# Sch_Add.net
KiCad netlist of a schematic drawn in Altium Designer
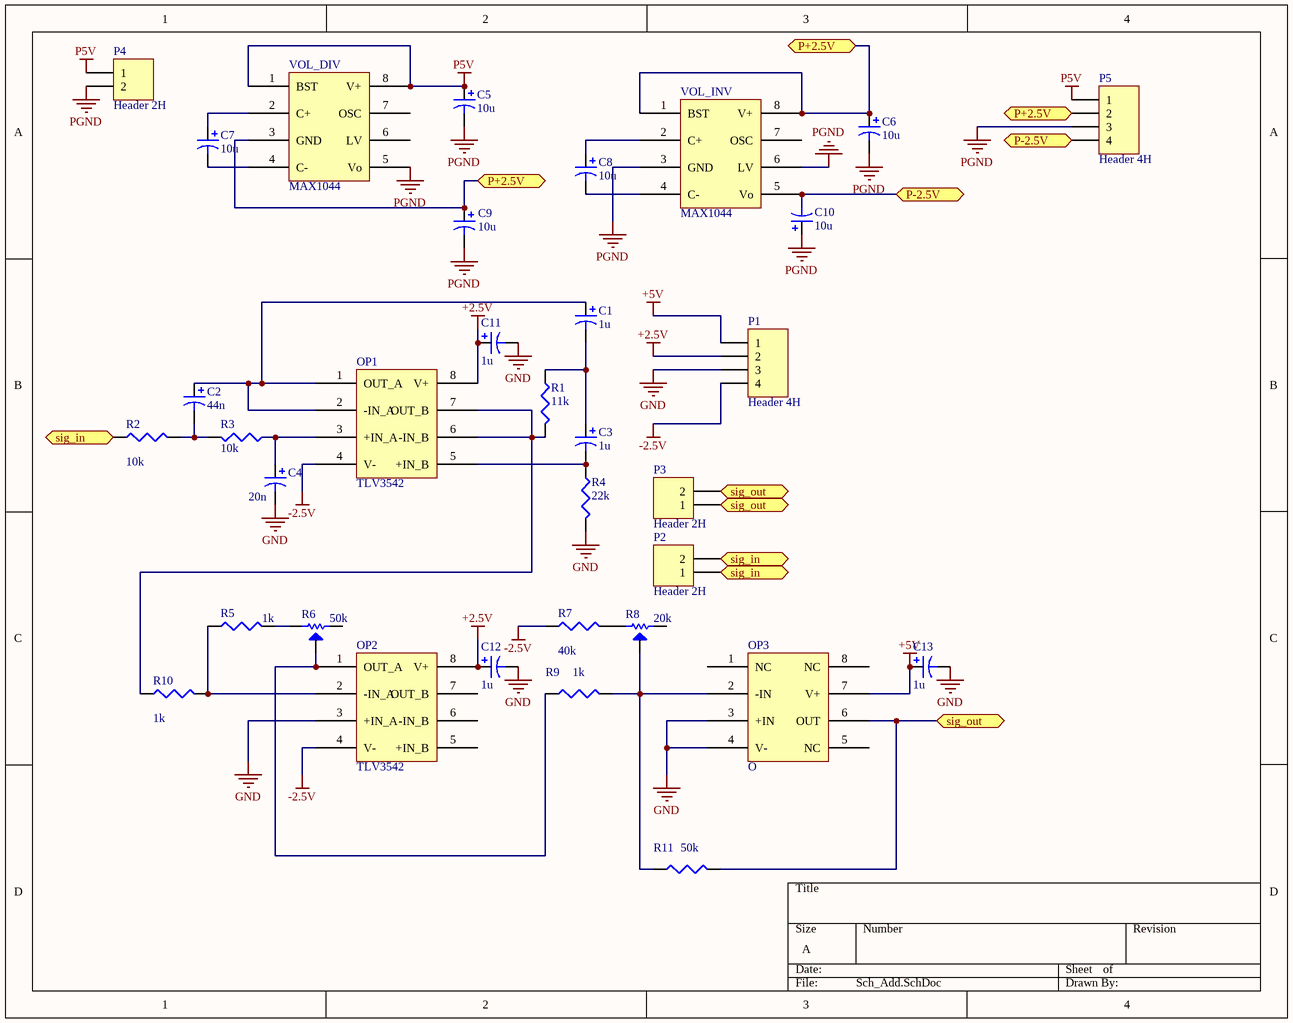
[diagram p0: Sch_Add.SchDoc]

(export (version "E")
  (design (tool "Eeschema 10.0.6"))
  (components
    (comp (ref "C1")
      (value "1u")
      (footprint "C0805")
      (description "Polarized Capacitor (Surface Mount)")
      (fields (field (name "Comment") "Cap Pol3") (field (name "PUBLISHER") "Altium Limited"))
      (libsource (lib "Miscellaneous Devices") (part "Cap Pol3"))
    )
    (comp (ref "C2")
      (value "44n")
      (footprint "C0805")
      (description "Polarized Capacitor (Surface Mount)")
      (fields (field (name "Comment") "Cap Pol3") (field (name "PUBLISHER") "Altium Limited"))
      (libsource (lib "Miscellaneous Devices") (part "Cap Pol3"))
    )
    (comp (ref "C3")
      (value "1u")
      (footprint "C0805")
      (description "Polarized Capacitor (Surface Mount)")
      (fields (field (name "Comment") "Cap Pol3") (field (name "PUBLISHER") "Altium Limited"))
      (libsource (lib "Miscellaneous Devices") (part "Cap Pol3"))
    )
    (comp (ref "C4")
      (value "20n")
      (footprint "C0805")
      (description "Polarized Capacitor (Surface Mount)")
      (fields (field (name "Comment") "Cap Pol3") (field (name "PUBLISHER") "Altium Limited"))
      (libsource (lib "Miscellaneous Devices") (part "Cap Pol3"))
    )
    (comp (ref "C5")
      (value "10u")
      (footprint "C0805")
      (description "Polarized Capacitor (Surface Mount)")
      (fields (field (name "Comment") "Cap Pol3") (field (name "PUBLISHER") "Altium Limited"))
      (libsource (lib "Miscellaneous Devices") (part "Cap Pol3"))
    )
    (comp (ref "C6")
      (value "10u")
      (footprint "C0805")
      (description "Polarized Capacitor (Surface Mount)")
      (fields (field (name "Comment") "Cap Pol3") (field (name "PUBLISHER") "Altium Limited"))
      (libsource (lib "Miscellaneous Devices") (part "Cap Pol3"))
    )
    (comp (ref "C7")
      (value "10u")
      (footprint "C0805")
      (description "Polarized Capacitor (Surface Mount)")
      (fields (field (name "Comment") "Cap Pol3") (field (name "PUBLISHER") "Altium Limited"))
      (libsource (lib "Miscellaneous Devices") (part "Cap Pol3"))
    )
    (comp (ref "C8")
      (value "10u")
      (footprint "C0805")
      (description "Polarized Capacitor (Surface Mount)")
      (fields (field (name "Comment") "Cap Pol3") (field (name "PUBLISHER") "Altium Limited"))
      (libsource (lib "Miscellaneous Devices") (part "Cap Pol3"))
    )
    (comp (ref "C9")
      (value "10u")
      (footprint "C0805")
      (description "Polarized Capacitor (Surface Mount)")
      (fields (field (name "Comment") "Cap Pol3") (field (name "PUBLISHER") "Altium Limited"))
      (libsource (lib "Miscellaneous Devices") (part "Cap Pol3"))
    )
    (comp (ref "C10")
      (value "10u")
      (footprint "C0805")
      (description "Polarized Capacitor (Surface Mount)")
      (fields (field (name "Comment") "Cap Pol3") (field (name "PUBLISHER") "Altium Limited"))
      (libsource (lib "Miscellaneous Devices") (part "Cap Pol3"))
    )
    (comp (ref "C11")
      (value "1u")
      (footprint "C0805")
      (description "Polarized Capacitor (Surface Mount)")
      (fields (field (name "Comment") "Cap Pol3") (field (name "PUBLISHER") "Altium Limited"))
      (libsource (lib "Miscellaneous Devices") (part "Cap Pol3"))
    )
    (comp (ref "C12")
      (value "1u")
      (footprint "C0805")
      (description "Polarized Capacitor (Surface Mount)")
      (fields (field (name "Comment") "Cap Pol3") (field (name "PUBLISHER") "Altium Limited"))
      (libsource (lib "Miscellaneous Devices") (part "Cap Pol3"))
    )
    (comp (ref "C13")
      (value "1u")
      (footprint "C0805")
      (description "Polarized Capacitor (Surface Mount)")
      (fields (field (name "Comment") "Cap Pol3") (field (name "PUBLISHER") "Altium Limited"))
      (libsource (lib "Miscellaneous Devices") (part "Cap Pol3"))
    )
    (comp (ref "OP1")
      (value "TLV3542")
      (footprint "SOIC127P600X175-8N")
      (libsource (lib "tlv3542") (part "TLV3542"))
    )
    (comp (ref "OP2")
      (value "TLV3542")
      (footprint "SOIC127P600X175-8N")
      (libsource (lib "tlv3542") (part "TLV3542"))
    )
    (comp (ref "OP3")
      (value "O")
      (footprint "SOIC127P600X175-8N")
      (libsource (lib "tlv3542") (part "OPA388IDR"))
    )
    (comp (ref "P1")
      (value "Header 4H")
      (footprint "HDR1X4H")
      (description "Header, 4-Pin, Right Angle")
      (fields (field (name "PUBLISHER") "Altium Limited"))
      (libsource (lib "Miscellaneous Connectors") (part "Header 4H"))
    )
    (comp (ref "P2")
      (value "Header 2H")
      (footprint "HDR1X2H")
      (description "Header, 2-Pin, Right Angle")
      (fields (field (name "PUBLISHER") "Altium Limited"))
      (libsource (lib "Miscellaneous Connectors") (part "Header 2H"))
    )
    (comp (ref "P3")
      (value "Header 2H")
      (footprint "HDR1X2H")
      (description "Header, 2-Pin, Right Angle")
      (fields (field (name "PUBLISHER") "Altium Limited"))
      (libsource (lib "Miscellaneous Connectors") (part "Header 2H"))
    )
    (comp (ref "P4")
      (value "Header 2H")
      (footprint "HDR1X2H")
      (description "Header, 2-Pin, Right Angle")
      (fields (field (name "PUBLISHER") "Altium Limited"))
      (libsource (lib "") (part "Header 2H_1"))
    )
    (comp (ref "P5")
      (value "Header 4H")
      (footprint "HDR1X4H")
      (description "Header, 4-Pin, Right Angle")
      (fields (field (name "PUBLISHER") "Altium Limited"))
      (libsource (lib "Miscellaneous Connectors") (part "Header 4H"))
    )
    (comp (ref "R1")
      (value "11k")
      (footprint "J1-0603")
      (description "Resistor")
      (fields (field (name "Comment") "Res3") (field (name "PUBLISHER") "Altium Limited"))
      (libsource (lib "Miscellaneous Devices") (part "Res3"))
    )
    (comp (ref "R2")
      (value "10k")
      (footprint "J1-0603")
      (description "Resistor")
      (fields (field (name "Comment") "Res3") (field (name "PUBLISHER") "Altium Limited"))
      (libsource (lib "Miscellaneous Devices") (part "Res3"))
    )
    (comp (ref "R3")
      (value "10k")
      (footprint "J1-0603")
      (description "Resistor")
      (fields (field (name "Comment") "Res3") (field (name "PUBLISHER") "Altium Limited"))
      (libsource (lib "Miscellaneous Devices") (part "Res3"))
    )
    (comp (ref "R4")
      (value "22k")
      (footprint "J1-0603")
      (description "Resistor")
      (fields (field (name "Comment") "Res3") (field (name "PUBLISHER") "Altium Limited"))
      (libsource (lib "Miscellaneous Devices") (part "Res3"))
    )
    (comp (ref "R5")
      (value "1k")
      (footprint "J1-0603")
      (description "Resistor")
      (fields (field (name "Comment") "Res3") (field (name "PUBLISHER") "Altium Limited"))
      (libsource (lib "Miscellaneous Devices") (part "Res3"))
    )
    (comp (ref "R6")
      (value "50k")
      (footprint "3362P")
      (fields (field (name "Comment") "5"))
      (libsource (lib "tlv3542") (part "Res_3362P"))
    )
    (comp (ref "R7")
      (value "40k")
      (footprint "J1-0603")
      (description "Resistor")
      (fields (field (name "Comment") "Res3") (field (name "PUBLISHER") "Altium Limited"))
      (libsource (lib "Miscellaneous Devices") (part "Res3"))
    )
    (comp (ref "R8")
      (value "20k")
      (footprint "3362P")
      (fields (field (name "Comment") "2"))
      (libsource (lib "tlv3542") (part "Res_3362P"))
    )
    (comp (ref "R9")
      (value "1k")
      (footprint "J1-0603")
      (description "Resistor")
      (fields (field (name "Comment") "Res3") (field (name "PUBLISHER") "Altium Limited"))
      (libsource (lib "Miscellaneous Devices") (part "Res3"))
    )
    (comp (ref "R10")
      (value "1k")
      (footprint "J1-0603")
      (description "Resistor")
      (fields (field (name "Comment") "Res3") (field (name "PUBLISHER") "Altium Limited"))
      (libsource (lib "Miscellaneous Devices") (part "Res3"))
    )
    (comp (ref "R11")
      (value "50k")
      (footprint "J1-0603")
      (description "Resistor")
      (fields (field (name "Comment") "Res3") (field (name "PUBLISHER") "Altium Limited"))
      (libsource (lib "Miscellaneous Devices") (part "Res3"))
    )
    (comp (ref "VOL_DIV")
      (value "MAX1044")
      (footprint "SOIC127P600X175-8N")
      (libsource (lib "tlv3542") (part "MAX1044"))
    )
    (comp (ref "VOL_INV")
      (value "MAX1044")
      (footprint "SOIC127P600X175-8N")
      (libsource (lib "tlv3542") (part "MAX1044"))
    )
  )
  (nets
    (net (code "1") (name "+2.5V") (class "Default")
      (node (ref "C11") (pin "1") (pinfunction "1_1") (pintype "passive"))
      (node (ref "C12") (pin "1") (pinfunction "1_1") (pintype "passive"))
      (node (ref "OP1") (pin "8") (pinfunction "V+_8") (pintype "passive"))
      (node (ref "OP2") (pin "8") (pinfunction "V+_8") (pintype "passive"))
      (node (ref "P1") (pin "2") (pinfunction "2_2") (pintype "passive"))
    )
    (net (code "2") (name "+5V") (class "Default")
      (node (ref "C13") (pin "1") (pinfunction "1_1") (pintype "passive"))
      (node (ref "OP3") (pin "7") (pinfunction "V+_7") (pintype "passive"))
      (node (ref "P1") (pin "1") (pinfunction "1_1") (pintype "passive"))
    )
    (net (code "3") (name "-2.5V") (class "Default")
      (node (ref "OP1") (pin "4") (pinfunction "V-_4") (pintype "passive"))
      (node (ref "OP2") (pin "4") (pinfunction "V-_4") (pintype "passive"))
      (node (ref "P1") (pin "4") (pinfunction "4_4") (pintype "passive"))
      (node (ref "R7") (pin "1") (pinfunction "1_1") (pintype "passive"))
    )
    (net (code "4") (name "/P+2.5V") (class "Default")
      (node (ref "C6") (pin "1") (pinfunction "1_1") (pintype "passive"))
      (node (ref "C9") (pin "1") (pinfunction "1_1") (pintype "passive"))
      (node (ref "P5") (pin "2") (pinfunction "2_2") (pintype "passive"))
      (node (ref "VOL_DIV") (pin "3") (pinfunction "GND_3") (pintype "passive"))
      (node (ref "VOL_INV") (pin "1") (pinfunction "BST_1") (pintype "passive"))
      (node (ref "VOL_INV") (pin "8") (pinfunction "V+_8") (pintype "passive"))
    )
    (net (code "5") (name "/P-2.5V") (class "Default")
      (node (ref "C10") (pin "2") (pinfunction "2_2") (pintype "passive"))
      (node (ref "P5") (pin "4") (pinfunction "4_4") (pintype "passive"))
      (node (ref "VOL_INV") (pin "5") (pinfunction "Vo_5") (pintype "passive"))
    )
    (net (code "6") (name "/sig_in") (class "Default")
      (node (ref "P2") (pin "1") (pinfunction "1_1") (pintype "passive"))
      (node (ref "P2") (pin "2") (pinfunction "2_2") (pintype "passive"))
      (node (ref "R2") (pin "1") (pinfunction "1_1") (pintype "passive"))
    )
    (net (code "7") (name "/sig_out") (class "Default")
      (node (ref "OP3") (pin "6") (pinfunction "OUT_6") (pintype "passive"))
      (node (ref "P3") (pin "1") (pinfunction "1_1") (pintype "passive"))
      (node (ref "P3") (pin "2") (pinfunction "2_2") (pintype "passive"))
      (node (ref "R11") (pin "2") (pinfunction "2_2") (pintype "passive"))
    )
    (net (code "8") (name "GND") (class "Default")
      (node (ref "C11") (pin "2") (pinfunction "2_2") (pintype "passive"))
      (node (ref "C12") (pin "2") (pinfunction "2_2") (pintype "passive"))
      (node (ref "C13") (pin "2") (pinfunction "2_2") (pintype "passive"))
      (node (ref "C4") (pin "2") (pinfunction "2_2") (pintype "passive"))
      (node (ref "OP2") (pin "3") (pinfunction "+IN_A_3") (pintype "passive"))
      (node (ref "OP3") (pin "3") (pinfunction "+IN_3") (pintype "passive"))
      (node (ref "OP3") (pin "4") (pinfunction "V-_4") (pintype "passive"))
      (node (ref "P1") (pin "3") (pinfunction "3_3") (pintype "passive"))
      (node (ref "R4") (pin "2") (pinfunction "2_2") (pintype "passive"))
    )
    (net (code "9") (name "Net-(C1-Pad2)") (class "Default")
      (node (ref "C1") (pin "2") (pinfunction "2_2") (pintype "passive"))
      (node (ref "C3") (pin "1") (pinfunction "1_1") (pintype "passive"))
      (node (ref "R1") (pin "1") (pinfunction "1_1") (pintype "passive"))
    )
    (net (code "10") (name "Net-(C2-Pad2)") (class "Default")
      (node (ref "C2") (pin "2") (pinfunction "2_2") (pintype "passive"))
      (node (ref "R2") (pin "2") (pinfunction "2_2") (pintype "passive"))
      (node (ref "R3") (pin "2") (pinfunction "2_2") (pintype "passive"))
    )
    (net (code "11") (name "Net-(OP1-+IN_A)") (class "Default")
      (node (ref "C4") (pin "1") (pinfunction "1_1") (pintype "passive"))
      (node (ref "OP1") (pin "3") (pinfunction "+IN_A_3") (pintype "passive"))
      (node (ref "R3") (pin "1") (pinfunction "1_1") (pintype "passive"))
    )
    (net (code "12") (name "Net-(OP1-+IN_B)") (class "Default")
      (node (ref "C3") (pin "2") (pinfunction "2_2") (pintype "passive"))
      (node (ref "OP1") (pin "5") (pinfunction "+IN_B_5") (pintype "passive"))
      (node (ref "R4") (pin "1") (pinfunction "1_1") (pintype "passive"))
    )
    (net (code "13") (name "Net-(OP1--IN_A)") (class "Default")
      (node (ref "C1") (pin "1") (pinfunction "1_1") (pintype "passive"))
      (node (ref "C2") (pin "1") (pinfunction "1_1") (pintype "passive"))
      (node (ref "OP1") (pin "1") (pinfunction "OUT_A_1") (pintype "passive"))
      (node (ref "OP1") (pin "2") (pinfunction "-IN_A_2") (pintype "passive"))
    )
    (net (code "14") (name "Net-(OP1--IN_B)") (class "Default")
      (node (ref "OP1") (pin "6") (pinfunction "-IN_B_6") (pintype "passive"))
      (node (ref "OP1") (pin "7") (pinfunction "OUT_B_7") (pintype "passive"))
      (node (ref "R1") (pin "2") (pinfunction "2_2") (pintype "passive"))
      (node (ref "R10") (pin "1") (pinfunction "1_1") (pintype "passive"))
    )
    (net (code "15") (name "Net-(OP2--IN_A)") (class "Default")
      (node (ref "OP2") (pin "2") (pinfunction "-IN_A_2") (pintype "passive"))
      (node (ref "R10") (pin "2") (pinfunction "2_2") (pintype "passive"))
      (node (ref "R5") (pin "1") (pinfunction "1_1") (pintype "passive"))
    )
    (net (code "16") (name "Net-(OP2-OUT_A)") (class "Default")
      (node (ref "OP2") (pin "1") (pinfunction "OUT_A_1") (pintype "passive"))
      (node (ref "R6") (pin "3") (pinfunction "3_3") (pintype "passive"))
      (node (ref "R9") (pin "1") (pinfunction "1_1") (pintype "passive"))
    )
    (net (code "17") (name "Net-(OP3--IN)") (class "Default")
      (node (ref "OP3") (pin "2") (pinfunction "-IN_2") (pintype "passive"))
      (node (ref "R11") (pin "1") (pinfunction "1_1") (pintype "passive"))
      (node (ref "R8") (pin "3") (pinfunction "3_3") (pintype "passive"))
      (node (ref "R9") (pin "2") (pinfunction "2_2") (pintype "passive"))
    )
    (net (code "18") (name "Net-(R5-Pad2)") (class "Default")
      (node (ref "R5") (pin "2") (pinfunction "2_2") (pintype "passive"))
      (node (ref "R6") (pin "1") (pinfunction "1_1") (pintype "passive"))
    )
    (net (code "19") (name "Net-(R7-Pad2)") (class "Default")
      (node (ref "R7") (pin "2") (pinfunction "2_2") (pintype "passive"))
      (node (ref "R8") (pin "1") (pinfunction "1_1") (pintype "passive"))
    )
    (net (code "20") (name "Net-(VOL_DIV-C+)") (class "Default")
      (node (ref "C7") (pin "1") (pinfunction "1_1") (pintype "passive"))
      (node (ref "VOL_DIV") (pin "2") (pinfunction "C+_2") (pintype "passive"))
    )
    (net (code "21") (name "Net-(VOL_DIV-C-)") (class "Default")
      (node (ref "C7") (pin "2") (pinfunction "2_2") (pintype "passive"))
      (node (ref "VOL_DIV") (pin "4") (pinfunction "C-_4") (pintype "passive"))
    )
    (net (code "22") (name "Net-(VOL_INV-C+)") (class "Default")
      (node (ref "C8") (pin "1") (pinfunction "1_1") (pintype "passive"))
      (node (ref "VOL_INV") (pin "2") (pinfunction "C+_2") (pintype "passive"))
    )
    (net (code "23") (name "Net-(VOL_INV-C-)") (class "Default")
      (node (ref "C8") (pin "2") (pinfunction "2_2") (pintype "passive"))
      (node (ref "VOL_INV") (pin "4") (pinfunction "C-_4") (pintype "passive"))
    )
    (net (code "24") (name "P5V") (class "Default")
      (node (ref "C5") (pin "1") (pinfunction "1_1") (pintype "passive"))
      (node (ref "P4") (pin "1") (pinfunction "1_1") (pintype "passive"))
      (node (ref "P5") (pin "1") (pinfunction "1_1") (pintype "passive"))
      (node (ref "VOL_DIV") (pin "1") (pinfunction "BST_1") (pintype "passive"))
      (node (ref "VOL_DIV") (pin "8") (pinfunction "V+_8") (pintype "passive"))
    )
    (net (code "25") (name "PGND") (class "Default")
      (node (ref "C10") (pin "1") (pinfunction "1_1") (pintype "passive"))
      (node (ref "C5") (pin "2") (pinfunction "2_2") (pintype "passive"))
      (node (ref "C6") (pin "2") (pinfunction "2_2") (pintype "passive"))
      (node (ref "C9") (pin "2") (pinfunction "2_2") (pintype "passive"))
      (node (ref "P4") (pin "2") (pinfunction "2_2") (pintype "passive"))
      (node (ref "P5") (pin "3") (pinfunction "3_3") (pintype "passive"))
      (node (ref "VOL_DIV") (pin "5") (pinfunction "Vo_5") (pintype "passive"))
      (node (ref "VOL_INV") (pin "3") (pinfunction "GND_3") (pintype "passive"))
      (node (ref "VOL_INV") (pin "6") (pinfunction "LV_6") (pintype "passive"))
    )
    (net (code "26") (name "unconnected-(OP2-+IN_B-Pad5)") (class "Default")
      (node (ref "OP2") (pin "5") (pinfunction "+IN_B_5") (pintype "passive"))
    )
    (net (code "27") (name "unconnected-(OP2--IN_B-Pad6)") (class "Default")
      (node (ref "OP2") (pin "6") (pinfunction "-IN_B_6") (pintype "passive"))
    )
    (net (code "28") (name "unconnected-(OP2-OUT_B-Pad7)") (class "Default")
      (node (ref "OP2") (pin "7") (pinfunction "OUT_B_7") (pintype "passive"))
    )
    (net (code "29") (name "unconnected-(OP3-NC-Pad1)") (class "Default")
      (node (ref "OP3") (pin "1") (pinfunction "NC_1") (pintype "passive"))
    )
    (net (code "30") (name "unconnected-(OP3-NC-Pad5)") (class "Default")
      (node (ref "OP3") (pin "5") (pinfunction "NC_5") (pintype "passive"))
    )
    (net (code "31") (name "unconnected-(OP3-NC-Pad8)") (class "Default")
      (node (ref "OP3") (pin "8") (pinfunction "NC_8") (pintype "passive"))
    )
    (net (code "32") (name "unconnected-(R6-Pad2)") (class "Default")
      (node (ref "R6") (pin "2") (pinfunction "2_2") (pintype "passive"))
    )
    (net (code "33") (name "unconnected-(R8-Pad2)") (class "Default")
      (node (ref "R8") (pin "2") (pinfunction "2_2") (pintype "passive"))
    )
    (net (code "34") (name "unconnected-(VOL_DIV-LV-Pad6)") (class "Default")
      (node (ref "VOL_DIV") (pin "6") (pinfunction "LV_6") (pintype "passive"))
    )
    (net (code "35") (name "unconnected-(VOL_DIV-OSC-Pad7)") (class "Default")
      (node (ref "VOL_DIV") (pin "7") (pinfunction "OSC_7") (pintype "passive"))
    )
    (net (code "36") (name "unconnected-(VOL_INV-OSC-Pad7)") (class "Default")
      (node (ref "VOL_INV") (pin "7") (pinfunction "OSC_7") (pintype "passive"))
    )
  )
)
